# USB_LiPolyCharger_SingleCell.net
KiCad netlist of a schematic drawn in EAGLE
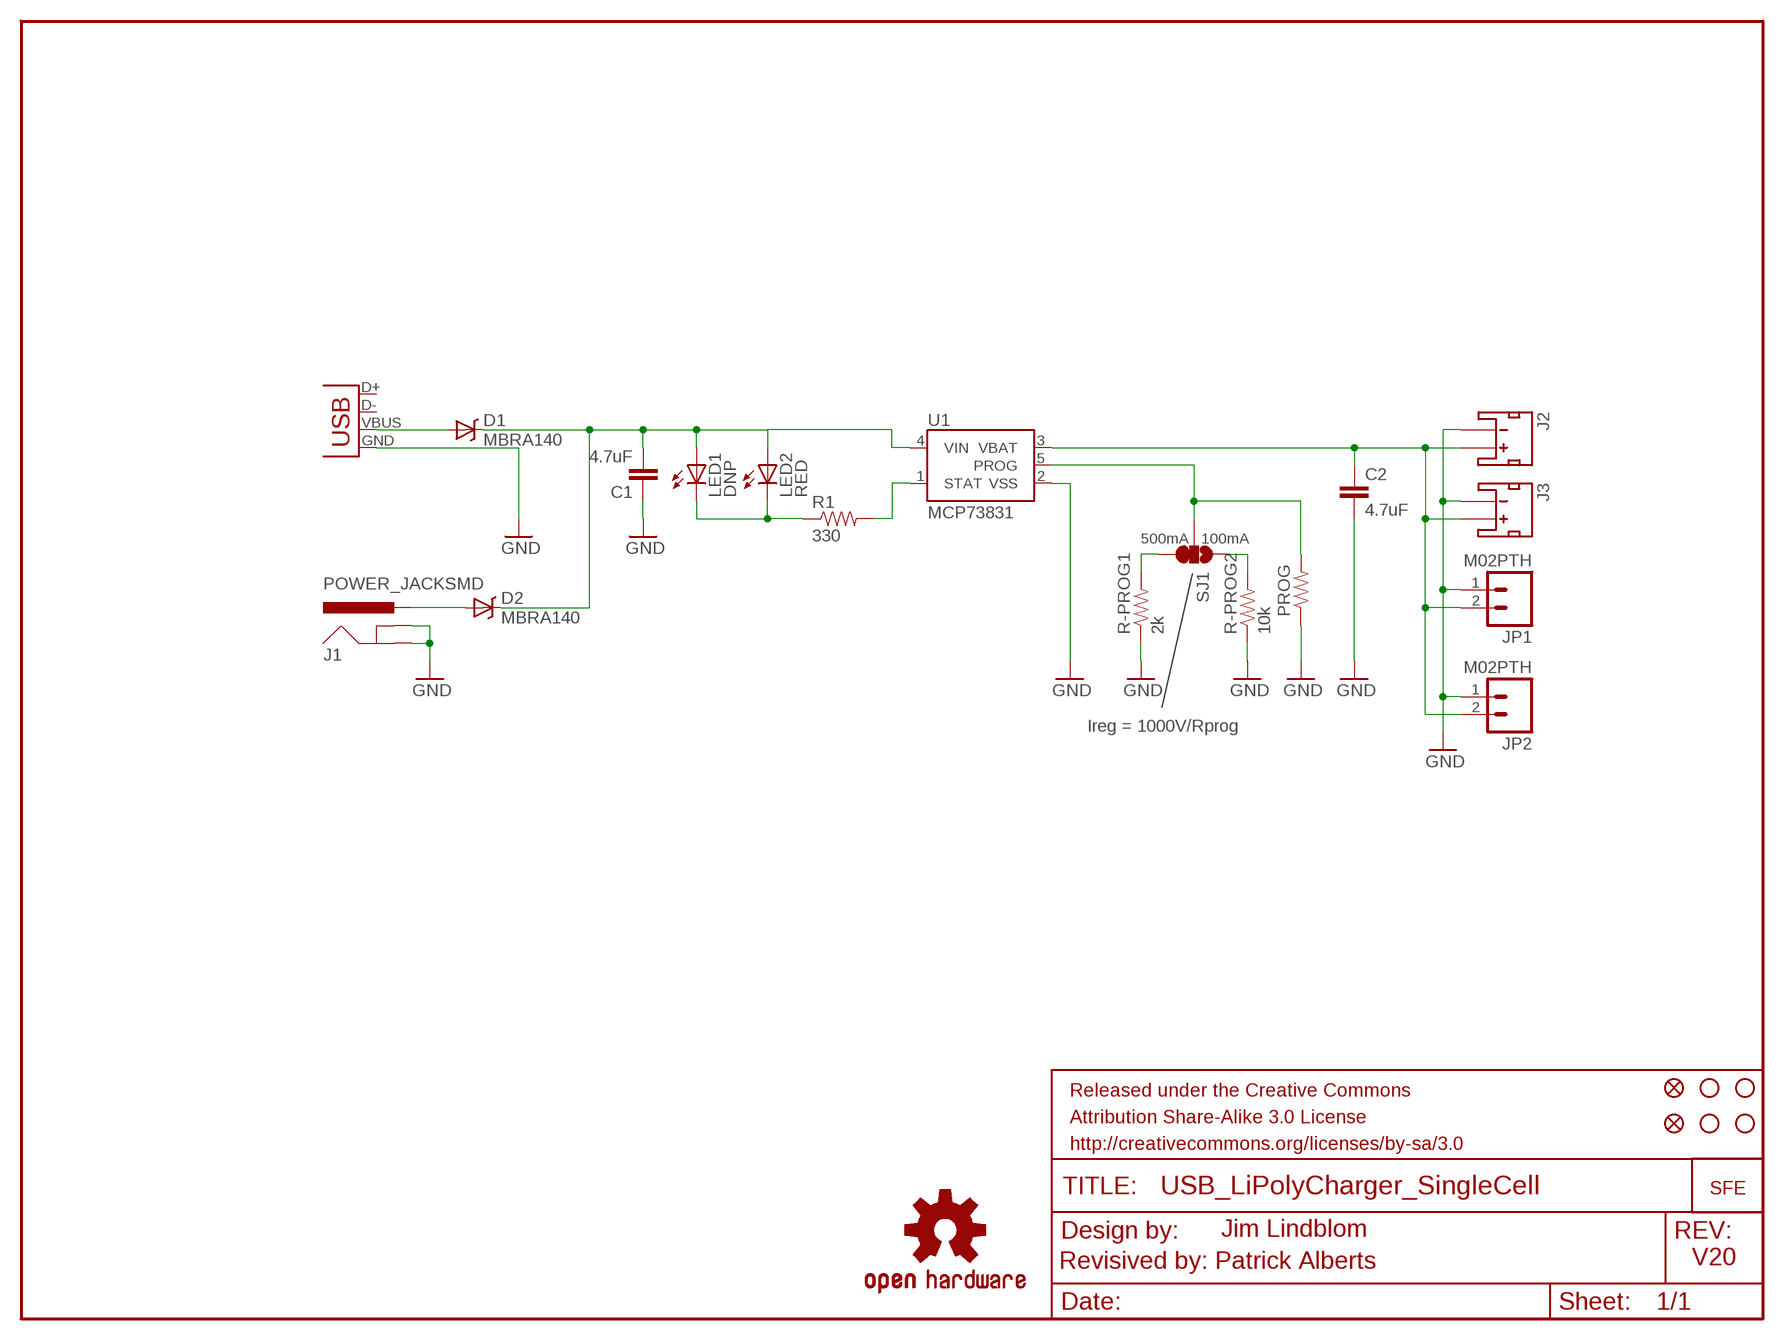
[diagram p0: schematic, sheet 1]

(export (version "E")
  (design (tool "Eeschema 10.0.6"))
  (components
    (comp (ref "C1")
      (value "4.7uF")
      (footprint "eagle-import:0603-CAP")
      (libsource (lib "eagle-import") (part "4.7UF-6.3V-10%(0603)0603"))
    )
    (comp (ref "C2")
      (value "4.7uF")
      (footprint "eagle-import:0603-CAP")
      (libsource (lib "eagle-import") (part "4.7UF-6.3V-10%(0603)0603"))
    )
    (comp (ref "D1")
      (value "MBRA140")
      (footprint "eagle-import:SMA-DIODE")
      (libsource (lib "eagle-import") (part "MBRA140"))
    )
    (comp (ref "D2")
      (value "MBRA140")
      (footprint "eagle-import:SMA-DIODE")
      (libsource (lib "eagle-import") (part "MBRA140"))
    )
    (comp (ref "FRAME1")
      (value "FRAME-LETTER")
      (footprint "eagle-import:CREATIVE_COMMONS")
      (libsource (lib "eagle-import") (part "FRAME-LETTER"))
    )
    (comp (ref "J1")
      (value "POWER_JACKSMD")
      (footprint "eagle-import:POWER_JACK_SMD")
      (libsource (lib "eagle-import") (part "POWER_JACKSMD"))
    )
    (comp (ref "J2")
      (value "JST_2MM_MALE")
      (footprint "eagle-import:JST-2-SMD")
      (libsource (lib "eagle-import") (part "JST_2MM_MALE"))
    )
    (comp (ref "J3")
      (value "JST_2MM_MALE")
      (footprint "eagle-import:JST-2-SMD")
      (libsource (lib "eagle-import") (part "JST_2MM_MALE"))
    )
    (comp (ref "JP1")
      (value "M02PTH")
      (footprint "eagle-import:1X02")
      (libsource (lib "eagle-import") (part "M02PTH"))
    )
    (comp (ref "JP2")
      (value "M02PTH")
      (footprint "eagle-import:1X02")
      (libsource (lib "eagle-import") (part "M02PTH"))
    )
    (comp (ref "JP7")
      (value "STAND-OFF")
      (footprint "eagle-import:STAND-OFF")
      (libsource (lib "eagle-import") (part "STAND-OFF"))
    )
    (comp (ref "JP8")
      (value "STAND-OFF")
      (footprint "eagle-import:STAND-OFF")
      (libsource (lib "eagle-import") (part "STAND-OFF"))
    )
    (comp (ref "JP9")
      (value "STAND-OFF")
      (footprint "eagle-import:STAND-OFF")
      (libsource (lib "eagle-import") (part "STAND-OFF"))
    )
    (comp (ref "JP10")
      (value "STAND-OFF")
      (footprint "eagle-import:STAND-OFF")
      (libsource (lib "eagle-import") (part "STAND-OFF"))
    )
    (comp (ref "JP11")
      (value "LOGO-SFENEW")
      (footprint "eagle-import:SFE-NEW-WEBLOGO")
      (libsource (lib "eagle-import") (part "LOGO-SFENEW"))
    )
    (comp (ref "JP12")
      (value "FIDUCIAL1X2")
      (footprint "eagle-import:FIDUCIAL-1X2")
      (libsource (lib "eagle-import") (part "FIDUCIAL1X2"))
    )
    (comp (ref "JP13")
      (value "FIDUCIAL1X2")
      (footprint "eagle-import:FIDUCIAL-1X2")
      (libsource (lib "eagle-import") (part "FIDUCIAL1X2"))
    )
    (comp (ref "LED1")
      (value "DNP")
      (footprint "eagle-import:LED3MM")
      (libsource (lib "eagle-import") (part "LED3MM"))
    )
    (comp (ref "LED2")
      (value "RED")
      (footprint "eagle-import:LED-0603")
      (libsource (lib "eagle-import") (part "LED-RED0603"))
    )
    (comp (ref "LOGO1")
      (value "OSHW-LOGOS")
      (footprint "eagle-import:OSHW-LOGO-S")
      (libsource (lib "eagle-import") (part "OSHW-LOGOS"))
    )
    (comp (ref "PROG")
      (value "RESISTORAXIAL-0.3")
      (footprint "eagle-import:AXIAL-0.3")
      (libsource (lib "eagle-import") (part "RESISTORAXIAL-0.3"))
    )
    (comp (ref "R-PROG1")
      (value "2k")
      (footprint "eagle-import:0603-RES")
      (libsource (lib "eagle-import") (part "2.0KOHM1/10W5%(0603)"))
    )
    (comp (ref "R-PROG2")
      (value "10k")
      (footprint "eagle-import:0603-RES")
      (libsource (lib "eagle-import") (part "10KOHM1/10W1%(0603)0603"))
    )
    (comp (ref "R1")
      (value "330")
      (footprint "eagle-import:0603-RES")
      (libsource (lib "eagle-import") (part "330OHM1/10W1%(0603)"))
    )
    (comp (ref "SJ1")
      (value "SOLDERJUMPER_2WAYS")
      (footprint "eagle-import:SJ_3")
      (libsource (lib "eagle-import") (part "SOLDERJUMPER_2WAYS"))
    )
    (comp (ref "U1")
      (value "MCP73831")
      (footprint "eagle-import:SOT23-5")
      (libsource (lib "eagle-import") (part "MCP73831"))
    )
    (comp (ref "X1")
      (value "USBSMD")
      (footprint "eagle-import:USB-MINIB")
      (libsource (lib "eagle-import") (part "USBSMD"))
    )
  )
  (nets
    (net (code "1") (name "GND") (class "Default")
      (node (ref "C1") (pin "1") (pinfunction "1_1") (pintype "passive"))
      (node (ref "C2") (pin "2") (pinfunction "2_2") (pintype "passive"))
      (node (ref "J1") (pin "GND") (pinfunction "GNDBREAK_GND") (pintype "bidirectional"))
      (node (ref "J1") (pin "P$4") (pinfunction "GND_P$4") (pintype "bidirectional"))
      (node (ref "J2") (pin "1") (pinfunction "-_1") (pintype "bidirectional"))
      (node (ref "J3") (pin "1") (pinfunction "-_1") (pintype "bidirectional"))
      (node (ref "JP1") (pin "1") (pinfunction "1_1") (pintype "passive"))
      (node (ref "JP2") (pin "1") (pinfunction "1_1") (pintype "passive"))
      (node (ref "PROG") (pin "P$1") (pinfunction "1_P$1") (pintype "passive"))
      (node (ref "R-PROG1") (pin "1") (pinfunction "1_1") (pintype "passive"))
      (node (ref "R-PROG2") (pin "1") (pinfunction "1_1") (pintype "passive"))
      (node (ref "U1") (pin "2") (pinfunction "VSS_2") (pintype "power_in"))
      (node (ref "X1") (pin "GND") (pinfunction "GND_GND") (pintype "bidirectional"))
    )
    (net (code "2") (name "Net-(D1-PadA)") (class "Default")
      (node (ref "D1") (pin "A") (pinfunction "A_A") (pintype "passive"))
      (node (ref "X1") (pin "VBUS") (pinfunction "VBUS_VBUS") (pintype "bidirectional"))
    )
    (net (code "3") (name "Net-(J1-PWR)") (class "Default")
      (node (ref "D2") (pin "A") (pinfunction "A_A") (pintype "passive"))
      (node (ref "J1") (pin "VIN0") (pinfunction "PWR_VIN0") (pintype "bidirectional"))
    )
    (net (code "4") (name "Net-(J2-+)") (class "Default")
      (node (ref "C2") (pin "1") (pinfunction "1_1") (pintype "passive"))
      (node (ref "J2") (pin "2") (pinfunction "+_2") (pintype "bidirectional"))
      (node (ref "J3") (pin "2") (pinfunction "+_2") (pintype "bidirectional"))
      (node (ref "JP1") (pin "2") (pinfunction "2_2") (pintype "passive"))
      (node (ref "JP2") (pin "2") (pinfunction "2_2") (pintype "passive"))
      (node (ref "U1") (pin "3") (pinfunction "VBAT_3") (pintype "power_in"))
    )
    (net (code "5") (name "Net-(LED1-C)") (class "Default")
      (node (ref "LED1") (pin "K") (pinfunction "C_K") (pintype "passive"))
      (node (ref "LED2") (pin "C") (pinfunction "C_C") (pintype "passive"))
      (node (ref "R1") (pin "1") (pinfunction "1_1") (pintype "passive"))
    )
    (net (code "6") (name "Net-(PROG-2)") (class "Default")
      (node (ref "PROG") (pin "P$2") (pinfunction "2_P$2") (pintype "passive"))
      (node (ref "SJ1") (pin "2") (pinfunction "2_2") (pintype "passive"))
      (node (ref "U1") (pin "5") (pinfunction "PROG_5") (pintype "input"))
    )
    (net (code "7") (name "Net-(R-PROG1-Pad2)") (class "Default")
      (node (ref "R-PROG1") (pin "2") (pinfunction "2_2") (pintype "passive"))
      (node (ref "SJ1") (pin "3") (pinfunction "3_3") (pintype "passive"))
    )
    (net (code "8") (name "Net-(R-PROG2-Pad2)") (class "Default")
      (node (ref "R-PROG2") (pin "2") (pinfunction "2_2") (pintype "passive"))
      (node (ref "SJ1") (pin "1") (pinfunction "1_1") (pintype "passive"))
    )
    (net (code "9") (name "Net-(U1-STAT)") (class "Default")
      (node (ref "R1") (pin "2") (pinfunction "2_2") (pintype "passive"))
      (node (ref "U1") (pin "1") (pinfunction "STAT_1") (pintype "output"))
    )
    (net (code "10") (name "Net-(U1-VIN)") (class "Default")
      (node (ref "C1") (pin "2") (pinfunction "2_2") (pintype "passive"))
      (node (ref "D1") (pin "C") (pinfunction "C_C") (pintype "passive"))
      (node (ref "D2") (pin "C") (pinfunction "C_C") (pintype "passive"))
      (node (ref "LED1") (pin "A") (pinfunction "A_A") (pintype "passive"))
      (node (ref "LED2") (pin "A") (pinfunction "A_A") (pintype "passive"))
      (node (ref "U1") (pin "4") (pinfunction "VIN_4") (pintype "power_in"))
    )
    (net (code "11") (name "unconnected-(J2-PAD1-PadNC1)") (class "Default")
      (node (ref "J2") (pin "NC1") (pinfunction "PAD1_NC1") (pintype "bidirectional"))
    )
    (net (code "12") (name "unconnected-(J2-PAD2-PadNC2)") (class "Default")
      (node (ref "J2") (pin "NC2") (pinfunction "PAD2_NC2") (pintype "bidirectional"))
    )
    (net (code "13") (name "unconnected-(J3-PAD1-PadNC1)") (class "Default")
      (node (ref "J3") (pin "NC1") (pinfunction "PAD1_NC1") (pintype "bidirectional"))
    )
    (net (code "14") (name "unconnected-(J3-PAD2-PadNC2)") (class "Default")
      (node (ref "J3") (pin "NC2") (pinfunction "PAD2_NC2") (pintype "bidirectional"))
    )
    (net (code "15") (name "unconnected-(X1-PadD+)") (class "Default")
      (node (ref "X1") (pin "D+") (pinfunction "D+_D+") (pintype "bidirectional"))
    )
    (net (code "16") (name "unconnected-(X1-PadD-)") (class "Default")
      (node (ref "X1") (pin "D-") (pinfunction "D-_D-") (pintype "bidirectional"))
    )
  )
)
